# obc-v2_MCU-POWER.net
KiCad netlist of a schematic drawn in Altium Designer
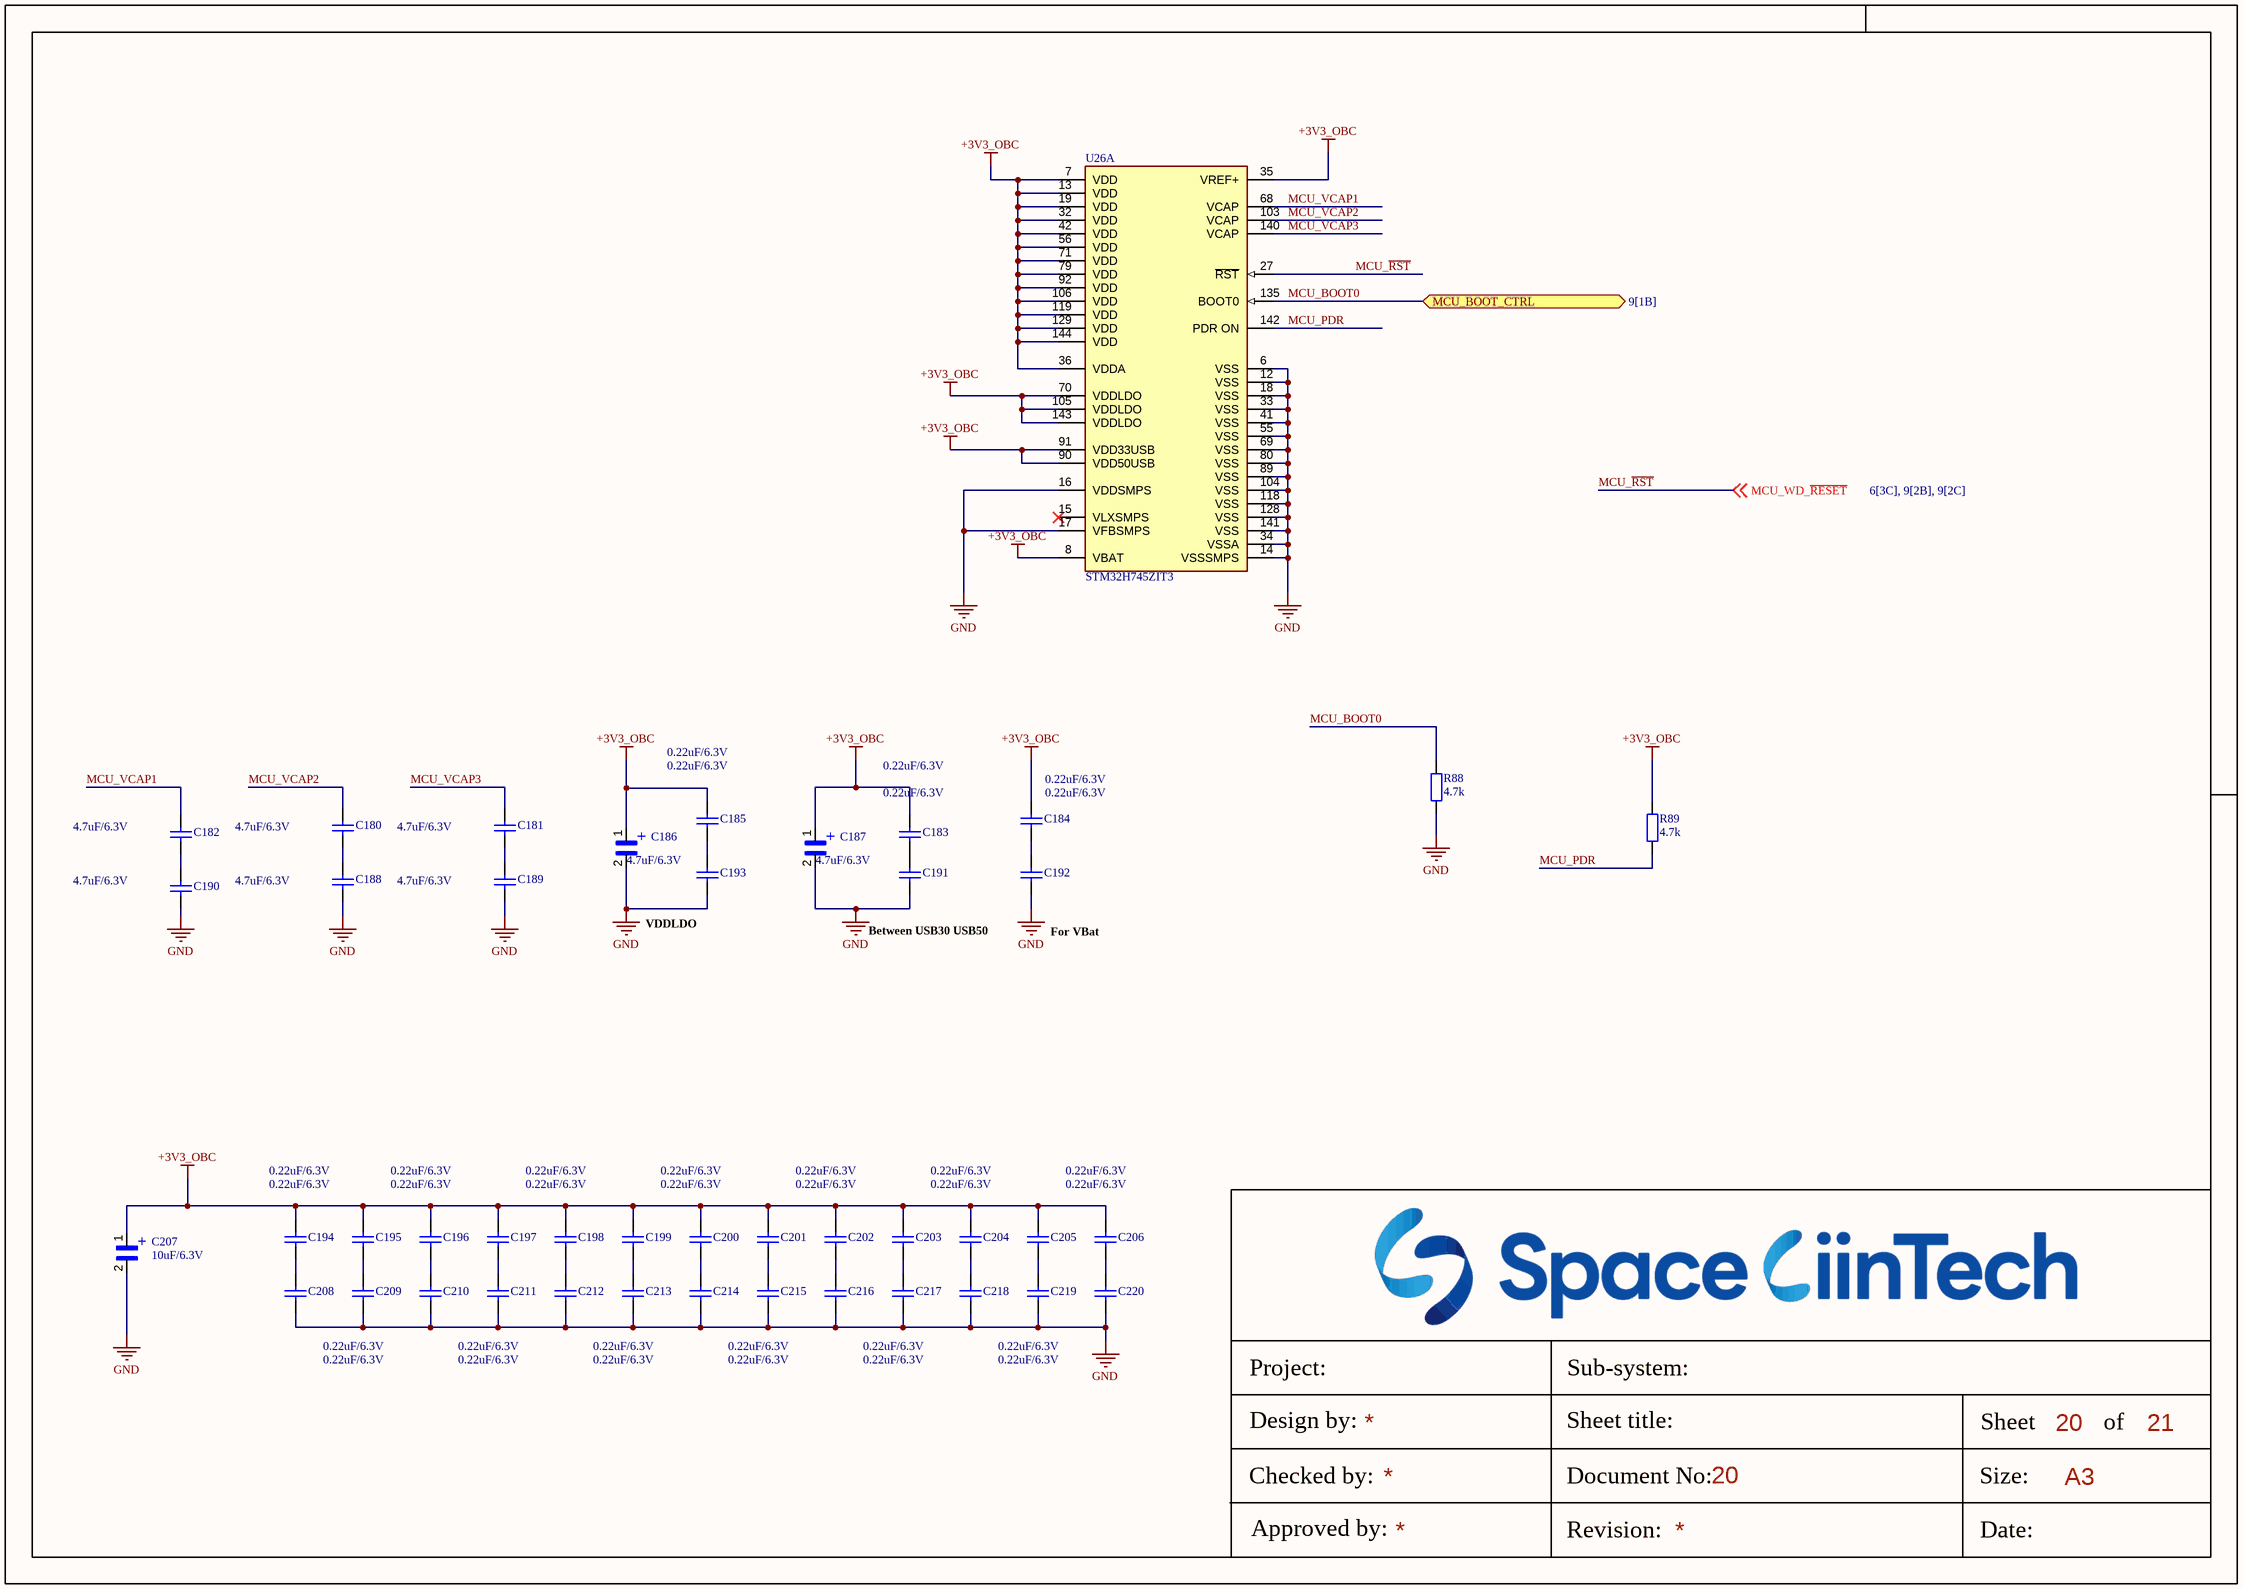
[diagram p0: obc-v2_MCU-POWER.SchDoc]

(export (version "E")
  (design (tool "Eeschema 10.0.6"))
  (components
    (comp (ref "C180")
      (value "4.7uF/6.3V")
      (footprint "CAP_C_1005X60")
      (description "4.7 µF ±20% 6.3V Ceramic Capacitor X7T 0402 (1005 Metric): GRT155D70J475ME13J")
      (libsource (lib "Altium_Lib_by_KhueNguyenCreator") (part "Tu 0402 33nF 10V"))
    )
    (comp (ref "C181")
      (value "4.7uF/6.3V")
      (footprint "CAP_C_1005X60")
      (description "4.7 µF ±20% 6.3V Ceramic Capacitor X7T 0402 (1005 Metric): GRT155D70J475ME13J")
      (libsource (lib "Altium_Lib_by_KhueNguyenCreator") (part "Tu 0402 33nF 10V"))
    )
    (comp (ref "C182")
      (value "4.7uF/6.3V")
      (footprint "CAP_C_1005X60")
      (description "4.7 µF ±20% 6.3V Ceramic Capacitor X7T 0402 (1005 Metric): GRT155D70J475ME13J")
      (libsource (lib "Altium_Lib_by_KhueNguyenCreator") (part "Tu 0402 33nF 10V"))
    )
    (comp (ref "C183")
      (value "0.22uF/6.3V")
      (footprint "CAP_C_1005X60")
      (description "CAPC")
      (libsource (lib "Altium_Lib_by_KhueNguyenCreator") (part "Tu 0402 33nF 10V"))
    )
    (comp (ref "C184")
      (value "0.22uF/6.3V")
      (footprint "CAP_C_1005X60")
      (description "CAPC")
      (libsource (lib "Altium_Lib_by_KhueNguyenCreator") (part "Tu 0402 33nF 10V"))
    )
    (comp (ref "C185")
      (value "0.22uF/6.3V")
      (footprint "CAP_C_1005X60")
      (description "4.7 µF ±20% 6.3V Ceramic Capacitor X7T 0402 (1005 Metric): GRT155D70J475ME13J")
      (libsource (lib "Altium_Lib_by_KhueNguyenCreator") (part "Tu 0402 33nF 10V"))
    )
    (comp (ref "C186")
      (value "4.7uF/6.3V")
      (footprint "CAP_MP_1608X90")
      (description "CAPP")
      (fields (field (name "MP") "TACL335M003RTA"))
      (libsource (lib "TACL335M003RTA") (part "TACL335M003RTA"))
    )
    (comp (ref "C187")
      (value "4.7uF/6.3V")
      (footprint "CAP_MP_1608X90")
      (description "CAPP")
      (fields (field (name "MP") "TACL335M003RTA"))
      (libsource (lib "TACL335M003RTA") (part "TACL335M003RTA"))
    )
    (comp (ref "C188")
      (value "4.7uF/6.3V")
      (footprint "CAP_C_1005X60")
      (description "4.7 µF ±20% 6.3V Ceramic Capacitor X7T 0402 (1005 Metric): GRT155D70J475ME13J")
      (libsource (lib "Altium_Lib_by_KhueNguyenCreator") (part "Tu 0402 33nF 10V"))
    )
    (comp (ref "C189")
      (value "4.7uF/6.3V")
      (footprint "CAP_C_1005X60")
      (description "4.7 µF ±20% 6.3V Ceramic Capacitor X7T 0402 (1005 Metric): GRT155D70J475ME13J")
      (libsource (lib "Altium_Lib_by_KhueNguyenCreator") (part "Tu 0402 33nF 10V"))
    )
    (comp (ref "C190")
      (value "4.7uF/6.3V")
      (footprint "CAP_C_1005X60")
      (description "4.7 µF ±20% 6.3V Ceramic Capacitor X7T 0402 (1005 Metric): GRT155D70J475ME13J")
      (libsource (lib "Altium_Lib_by_KhueNguyenCreator") (part "Tu 0402 33nF 10V"))
    )
    (comp (ref "C191")
      (value "0.22uF/6.3V")
      (footprint "CAP_C_1005X60")
      (description "CAPC")
      (libsource (lib "Altium_Lib_by_KhueNguyenCreator") (part "Tu 0402 33nF 10V"))
    )
    (comp (ref "C192")
      (value "0.22uF/6.3V")
      (footprint "CAP_C_1005X60")
      (description "CAPC")
      (libsource (lib "Altium_Lib_by_KhueNguyenCreator") (part "Tu 0402 33nF 10V"))
    )
    (comp (ref "C193")
      (value "0.22uF/6.3V")
      (footprint "CAP_C_1005X60")
      (description "4.7 µF ±20% 6.3V Ceramic Capacitor X7T 0402 (1005 Metric): GRT155D70J475ME13J")
      (libsource (lib "Altium_Lib_by_KhueNguyenCreator") (part "Tu 0402 33nF 10V"))
    )
    (comp (ref "C194")
      (value "0.22uF/6.3V")
      (footprint "CAP_C_1005X60")
      (description "CAPC")
      (libsource (lib "Altium_Lib_by_KhueNguyenCreator") (part "Tu 0402 33nF 10V"))
    )
    (comp (ref "C195")
      (value "0.22uF/6.3V")
      (footprint "CAP_C_1005X60")
      (description "CAPC")
      (libsource (lib "Altium_Lib_by_KhueNguyenCreator") (part "Tu 0402 33nF 10V"))
    )
    (comp (ref "C196")
      (value "0.22uF/6.3V")
      (footprint "CAP_C_1005X60")
      (description "CAPC")
      (libsource (lib "Altium_Lib_by_KhueNguyenCreator") (part "Tu 0402 33nF 10V"))
    )
    (comp (ref "C197")
      (value "0.22uF/6.3V")
      (footprint "CAP_C_1005X60")
      (description "CAPC")
      (libsource (lib "Altium_Lib_by_KhueNguyenCreator") (part "Tu 0402 33nF 10V"))
    )
    (comp (ref "C198")
      (value "0.22uF/6.3V")
      (footprint "CAP_C_1005X60")
      (description "CAPC")
      (libsource (lib "Altium_Lib_by_KhueNguyenCreator") (part "Tu 0402 33nF 10V"))
    )
    (comp (ref "C199")
      (value "0.22uF/6.3V")
      (footprint "CAP_C_1005X60")
      (description "CAPC")
      (libsource (lib "Altium_Lib_by_KhueNguyenCreator") (part "Tu 0402 33nF 10V"))
    )
    (comp (ref "C200")
      (value "0.22uF/6.3V")
      (footprint "CAP_C_1005X60")
      (description "CAPC")
      (libsource (lib "Altium_Lib_by_KhueNguyenCreator") (part "Tu 0402 33nF 10V"))
    )
    (comp (ref "C201")
      (value "0.22uF/6.3V")
      (footprint "CAP_C_1005X60")
      (description "CAPC")
      (libsource (lib "Altium_Lib_by_KhueNguyenCreator") (part "Tu 0402 33nF 10V"))
    )
    (comp (ref "C202")
      (value "0.22uF/6.3V")
      (footprint "CAP_C_1005X60")
      (description "CAPC")
      (libsource (lib "Altium_Lib_by_KhueNguyenCreator") (part "Tu 0402 33nF 10V"))
    )
    (comp (ref "C203")
      (value "0.22uF/6.3V")
      (footprint "CAP_C_1005X60")
      (description "CAPC")
      (libsource (lib "Altium_Lib_by_KhueNguyenCreator") (part "Tu 0402 33nF 10V"))
    )
    (comp (ref "C204")
      (value "0.22uF/6.3V")
      (footprint "CAP_C_1005X60")
      (description "CAPC")
      (libsource (lib "Altium_Lib_by_KhueNguyenCreator") (part "Tu 0402 33nF 10V"))
    )
    (comp (ref "C205")
      (value "0.22uF/6.3V")
      (footprint "CAP_C_1005X60")
      (description "CAPC")
      (libsource (lib "Altium_Lib_by_KhueNguyenCreator") (part "Tu 0402 33nF 10V"))
    )
    (comp (ref "C206")
      (value "0.22uF/6.3V")
      (footprint "CAP_C_1005X60")
      (description "CAPC")
      (libsource (lib "Altium_Lib_by_KhueNguyenCreator") (part "Tu 0402 33nF 10V"))
    )
    (comp (ref "C207")
      (value "10uF/6.3V")
      (footprint "CAP_MP_2012X170")
      (description "CAPP")
      (fields (field (name "MP") "TACR686M003RTA") (field (name "MF") "AVX"))
      (libsource (lib "TACR686M003RTA") (part "TACR686M003RTA"))
    )
    (comp (ref "C208")
      (value "0.22uF/6.3V")
      (footprint "CAP_C_1005X60")
      (description "CAPC")
      (libsource (lib "Altium_Lib_by_KhueNguyenCreator") (part "Tu 0402 33nF 10V"))
    )
    (comp (ref "C209")
      (value "0.22uF/6.3V")
      (footprint "CAP_C_1005X60")
      (description "CAPC")
      (libsource (lib "Altium_Lib_by_KhueNguyenCreator") (part "Tu 0402 33nF 10V"))
    )
    (comp (ref "C210")
      (value "0.22uF/6.3V")
      (footprint "CAP_C_1005X60")
      (description "CAPC")
      (libsource (lib "Altium_Lib_by_KhueNguyenCreator") (part "Tu 0402 33nF 10V"))
    )
    (comp (ref "C211")
      (value "0.22uF/6.3V")
      (footprint "CAP_C_1005X60")
      (description "CAPC")
      (libsource (lib "Altium_Lib_by_KhueNguyenCreator") (part "Tu 0402 33nF 10V"))
    )
    (comp (ref "C212")
      (value "0.22uF/6.3V")
      (footprint "CAP_C_1005X60")
      (description "CAPC")
      (libsource (lib "Altium_Lib_by_KhueNguyenCreator") (part "Tu 0402 33nF 10V"))
    )
    (comp (ref "C213")
      (value "0.22uF/6.3V")
      (footprint "CAP_C_1005X60")
      (description "CAPC")
      (libsource (lib "Altium_Lib_by_KhueNguyenCreator") (part "Tu 0402 33nF 10V"))
    )
    (comp (ref "C214")
      (value "0.22uF/6.3V")
      (footprint "CAP_C_1005X60")
      (description "CAPC")
      (libsource (lib "Altium_Lib_by_KhueNguyenCreator") (part "Tu 0402 33nF 10V"))
    )
    (comp (ref "C215")
      (value "0.22uF/6.3V")
      (footprint "CAP_C_1005X60")
      (description "CAPC")
      (libsource (lib "Altium_Lib_by_KhueNguyenCreator") (part "Tu 0402 33nF 10V"))
    )
    (comp (ref "C216")
      (value "0.22uF/6.3V")
      (footprint "CAP_C_1005X60")
      (description "CAPC")
      (libsource (lib "Altium_Lib_by_KhueNguyenCreator") (part "Tu 0402 33nF 10V"))
    )
    (comp (ref "C217")
      (value "0.22uF/6.3V")
      (footprint "CAP_C_1005X60")
      (description "CAPC")
      (libsource (lib "Altium_Lib_by_KhueNguyenCreator") (part "Tu 0402 33nF 10V"))
    )
    (comp (ref "C218")
      (value "0.22uF/6.3V")
      (footprint "CAP_C_1005X60")
      (description "CAPC")
      (libsource (lib "Altium_Lib_by_KhueNguyenCreator") (part "Tu 0402 33nF 10V"))
    )
    (comp (ref "C219")
      (value "0.22uF/6.3V")
      (footprint "CAP_C_1005X60")
      (description "CAPC")
      (libsource (lib "Altium_Lib_by_KhueNguyenCreator") (part "Tu 0402 33nF 10V"))
    )
    (comp (ref "C220")
      (value "0.22uF/6.3V")
      (footprint "CAP_C_1005X60")
      (description "CAPC")
      (libsource (lib "Altium_Lib_by_KhueNguyenCreator") (part "Tu 0402 33nF 10V"))
    )
    (comp (ref "R88")
      (value "4.7k")
      (footprint "RES_C_1608X60")
      (description "RES")
      (libsource (lib "Altium_Lib_by_KhueNguyenCreator") (part "Tro 0603 1% 10k"))
    )
    (comp (ref "R89")
      (value "4.7k")
      (footprint "RES_C_1608X60")
      (description "RES")
      (libsource (lib "Altium_Lib_by_KhueNguyenCreator") (part "Tro 0603 1% 10k"))
    )
    (comp (ref "U26")
      (value "STM32H745ZIT3")
      (footprint "FP-LQFP144-1A-MFG")
      (description "HIGH-PERFORMANCE AND DSP WITH DP")
      (fields
        (field (name "MANUFACTURER PART NUMBER") "STM32H745ZIT6")
        (field (name "OCTOPART") "https://octopart.com/stm32h745zit6-stmicroelectronics-100293939")
      )
      (libsource (lib "Altium Content Vault") (part "f5432ce9894f79c0085309acf87c031"))
    )
  )
  (nets
    (net (code "1") (name "+3V3_OBC") (class "Default")
      (node (ref "C183") (pin "1") (pinfunction "1_1") (pintype "passive"))
      (node (ref "C184") (pin "1") (pinfunction "1_1") (pintype "passive"))
      (node (ref "C185") (pin "1") (pinfunction "1_1") (pintype "passive"))
      (node (ref "C186") (pin "1") (pinfunction "1_1") (pintype "passive"))
      (node (ref "C187") (pin "1") (pinfunction "1_1") (pintype "passive"))
      (node (ref "C194") (pin "1") (pinfunction "1_1") (pintype "passive"))
      (node (ref "C195") (pin "1") (pinfunction "1_1") (pintype "passive"))
      (node (ref "C196") (pin "1") (pinfunction "1_1") (pintype "passive"))
      (node (ref "C197") (pin "1") (pinfunction "1_1") (pintype "passive"))
      (node (ref "C198") (pin "1") (pinfunction "1_1") (pintype "passive"))
      (node (ref "C199") (pin "1") (pinfunction "1_1") (pintype "passive"))
      (node (ref "C200") (pin "1") (pinfunction "1_1") (pintype "passive"))
      (node (ref "C201") (pin "1") (pinfunction "1_1") (pintype "passive"))
      (node (ref "C202") (pin "1") (pinfunction "1_1") (pintype "passive"))
      (node (ref "C203") (pin "1") (pinfunction "1_1") (pintype "passive"))
      (node (ref "C204") (pin "1") (pinfunction "1_1") (pintype "passive"))
      (node (ref "C205") (pin "1") (pinfunction "1_1") (pintype "passive"))
      (node (ref "C206") (pin "1") (pinfunction "1_1") (pintype "passive"))
      (node (ref "C207") (pin "1") (pinfunction "1_1") (pintype "passive"))
      (node (ref "R89") (pin "1") (pinfunction "1_1") (pintype "passive"))
      (node (ref "U26") (pin "105") (pinfunction "VDDLDO_105") (pintype "power_in"))
      (node (ref "U26") (pin "106") (pinfunction "VDD_106") (pintype "power_in"))
      (node (ref "U26") (pin "119") (pinfunction "VDD_119") (pintype "power_in"))
      (node (ref "U26") (pin "129") (pinfunction "VDD_129") (pintype "power_in"))
      (node (ref "U26") (pin "13") (pinfunction "VDD_13") (pintype "power_in"))
      (node (ref "U26") (pin "143") (pinfunction "VDDLDO_143") (pintype "power_in"))
      (node (ref "U26") (pin "144") (pinfunction "VDD_144") (pintype "power_in"))
      (node (ref "U26") (pin "19") (pinfunction "VDD_19") (pintype "power_in"))
      (node (ref "U26") (pin "32") (pinfunction "VDD_32") (pintype "power_in"))
      (node (ref "U26") (pin "35") (pinfunction "VREF+_35") (pintype "power_in"))
      (node (ref "U26") (pin "36") (pinfunction "VDDA_36") (pintype "power_in"))
      (node (ref "U26") (pin "42") (pinfunction "VDD_42") (pintype "power_in"))
      (node (ref "U26") (pin "56") (pinfunction "VDD_56") (pintype "power_in"))
      (node (ref "U26") (pin "7") (pinfunction "VDD_7") (pintype "power_in"))
      (node (ref "U26") (pin "70") (pinfunction "VDDLDO_70") (pintype "power_in"))
      (node (ref "U26") (pin "71") (pinfunction "VDD_71") (pintype "power_in"))
      (node (ref "U26") (pin "79") (pinfunction "VDD_79") (pintype "power_in"))
      (node (ref "U26") (pin "8") (pinfunction "VBAT_8") (pintype "power_in"))
      (node (ref "U26") (pin "90") (pinfunction "VDD50USB_90") (pintype "power_in"))
      (node (ref "U26") (pin "91") (pinfunction "VDD33USB_91") (pintype "power_in"))
      (node (ref "U26") (pin "92") (pinfunction "VDD_92") (pintype "power_in"))
    )
    (net (code "2") (name "/MCU_BOOT0") (class "Default")
      (node (ref "R88") (pin "2") (pinfunction "2_2") (pintype "passive"))
      (node (ref "U26") (pin "135") (pinfunction "BOOT0_135") (pintype "input"))
    )
    (net (code "3") (name "/MCU_PDR") (class "Default")
      (node (ref "R89") (pin "2") (pinfunction "2_2") (pintype "passive"))
      (node (ref "U26") (pin "142") (pinfunction "PDR_ON_142") (pintype "passive"))
    )
    (net (code "4") (name "/MCU_VCAP1") (class "Default")
      (node (ref "C182") (pin "1") (pinfunction "1_1") (pintype "passive"))
      (node (ref "U26") (pin "68") (pinfunction "VCAP_68") (pintype "passive"))
    )
    (net (code "5") (name "/MCU_VCAP2") (class "Default")
      (node (ref "C180") (pin "1") (pinfunction "1_1") (pintype "passive"))
      (node (ref "U26") (pin "103") (pinfunction "VCAP_103") (pintype "passive"))
    )
    (net (code "6") (name "/MCU_VCAP3") (class "Default")
      (node (ref "C181") (pin "1") (pinfunction "1_1") (pintype "passive"))
      (node (ref "U26") (pin "140") (pinfunction "VCAP_140") (pintype "passive"))
    )
    (net (code "7") (name "GND") (class "Default")
      (node (ref "C186") (pin "2") (pinfunction "2_2") (pintype "passive"))
      (node (ref "C187") (pin "2") (pinfunction "2_2") (pintype "passive"))
      (node (ref "C188") (pin "2") (pinfunction "2_2") (pintype "passive"))
      (node (ref "C189") (pin "2") (pinfunction "2_2") (pintype "passive"))
      (node (ref "C190") (pin "2") (pinfunction "2_2") (pintype "passive"))
      (node (ref "C191") (pin "2") (pinfunction "2_2") (pintype "passive"))
      (node (ref "C192") (pin "2") (pinfunction "2_2") (pintype "passive"))
      (node (ref "C193") (pin "2") (pinfunction "2_2") (pintype "passive"))
      (node (ref "C207") (pin "2") (pinfunction "2_2") (pintype "passive"))
      (node (ref "C208") (pin "2") (pinfunction "2_2") (pintype "passive"))
      (node (ref "C209") (pin "2") (pinfunction "2_2") (pintype "passive"))
      (node (ref "C210") (pin "2") (pinfunction "2_2") (pintype "passive"))
      (node (ref "C211") (pin "2") (pinfunction "2_2") (pintype "passive"))
      (node (ref "C212") (pin "2") (pinfunction "2_2") (pintype "passive"))
      (node (ref "C213") (pin "2") (pinfunction "2_2") (pintype "passive"))
      (node (ref "C214") (pin "2") (pinfunction "2_2") (pintype "passive"))
      (node (ref "C215") (pin "2") (pinfunction "2_2") (pintype "passive"))
      (node (ref "C216") (pin "2") (pinfunction "2_2") (pintype "passive"))
      (node (ref "C217") (pin "2") (pinfunction "2_2") (pintype "passive"))
      (node (ref "C218") (pin "2") (pinfunction "2_2") (pintype "passive"))
      (node (ref "C219") (pin "2") (pinfunction "2_2") (pintype "passive"))
      (node (ref "C220") (pin "2") (pinfunction "2_2") (pintype "passive"))
      (node (ref "R88") (pin "1") (pinfunction "1_1") (pintype "passive"))
      (node (ref "U26") (pin "104") (pinfunction "VSS_104") (pintype "power_in"))
      (node (ref "U26") (pin "118") (pinfunction "VSS_118") (pintype "power_in"))
      (node (ref "U26") (pin "12") (pinfunction "VSS_12") (pintype "power_in"))
      (node (ref "U26") (pin "128") (pinfunction "VSS_128") (pintype "power_in"))
      (node (ref "U26") (pin "14") (pinfunction "VSSSMPS_14") (pintype "power_in"))
      (node (ref "U26") (pin "141") (pinfunction "VSS_141") (pintype "power_in"))
      (node (ref "U26") (pin "16") (pinfunction "VDDSMPS_16") (pintype "power_in"))
      (node (ref "U26") (pin "17") (pinfunction "VFBSMPS_17") (pintype "power_in"))
      (node (ref "U26") (pin "18") (pinfunction "VSS_18") (pintype "power_in"))
      (node (ref "U26") (pin "33") (pinfunction "VSS_33") (pintype "power_in"))
      (node (ref "U26") (pin "34") (pinfunction "VSSA_34") (pintype "power_in"))
      (node (ref "U26") (pin "41") (pinfunction "VSS_41") (pintype "power_in"))
      (node (ref "U26") (pin "55") (pinfunction "VSS_55") (pintype "power_in"))
      (node (ref "U26") (pin "6") (pinfunction "VSS_6") (pintype "power_in"))
      (node (ref "U26") (pin "69") (pinfunction "VSS_69") (pintype "power_in"))
      (node (ref "U26") (pin "80") (pinfunction "VSS_80") (pintype "power_in"))
      (node (ref "U26") (pin "89") (pinfunction "VSS_89") (pintype "power_in"))
    )
    (net (code "8") (name "MCU_WD_~{RESET}") (class "Default")
      (node (ref "U26") (pin "27") (pinfunction "~{RST}_27") (pintype "input"))
    )
    (net (code "9") (name "Net-(C180-Pad2)") (class "Default")
      (node (ref "C180") (pin "2") (pinfunction "2_2") (pintype "passive"))
      (node (ref "C188") (pin "1") (pinfunction "1_1") (pintype "passive"))
    )
    (net (code "10") (name "Net-(C181-Pad2)") (class "Default")
      (node (ref "C181") (pin "2") (pinfunction "2_2") (pintype "passive"))
      (node (ref "C189") (pin "1") (pinfunction "1_1") (pintype "passive"))
    )
    (net (code "11") (name "Net-(C182-Pad2)") (class "Default")
      (node (ref "C182") (pin "2") (pinfunction "2_2") (pintype "passive"))
      (node (ref "C190") (pin "1") (pinfunction "1_1") (pintype "passive"))
    )
    (net (code "12") (name "Net-(C183-Pad2)") (class "Default")
      (node (ref "C183") (pin "2") (pinfunction "2_2") (pintype "passive"))
      (node (ref "C191") (pin "1") (pinfunction "1_1") (pintype "passive"))
    )
    (net (code "13") (name "Net-(C184-Pad2)") (class "Default")
      (node (ref "C184") (pin "2") (pinfunction "2_2") (pintype "passive"))
      (node (ref "C192") (pin "1") (pinfunction "1_1") (pintype "passive"))
    )
    (net (code "14") (name "Net-(C185-Pad2)") (class "Default")
      (node (ref "C185") (pin "2") (pinfunction "2_2") (pintype "passive"))
      (node (ref "C193") (pin "1") (pinfunction "1_1") (pintype "passive"))
    )
    (net (code "15") (name "Net-(C194-Pad2)") (class "Default")
      (node (ref "C194") (pin "2") (pinfunction "2_2") (pintype "passive"))
      (node (ref "C208") (pin "1") (pinfunction "1_1") (pintype "passive"))
    )
    (net (code "16") (name "Net-(C195-Pad2)") (class "Default")
      (node (ref "C195") (pin "2") (pinfunction "2_2") (pintype "passive"))
      (node (ref "C209") (pin "1") (pinfunction "1_1") (pintype "passive"))
    )
    (net (code "17") (name "Net-(C196-Pad2)") (class "Default")
      (node (ref "C196") (pin "2") (pinfunction "2_2") (pintype "passive"))
      (node (ref "C210") (pin "1") (pinfunction "1_1") (pintype "passive"))
    )
    (net (code "18") (name "Net-(C197-Pad2)") (class "Default")
      (node (ref "C197") (pin "2") (pinfunction "2_2") (pintype "passive"))
      (node (ref "C211") (pin "1") (pinfunction "1_1") (pintype "passive"))
    )
    (net (code "19") (name "Net-(C198-Pad2)") (class "Default")
      (node (ref "C198") (pin "2") (pinfunction "2_2") (pintype "passive"))
      (node (ref "C212") (pin "1") (pinfunction "1_1") (pintype "passive"))
    )
    (net (code "20") (name "Net-(C199-Pad2)") (class "Default")
      (node (ref "C199") (pin "2") (pinfunction "2_2") (pintype "passive"))
      (node (ref "C213") (pin "1") (pinfunction "1_1") (pintype "passive"))
    )
    (net (code "21") (name "Net-(C200-Pad2)") (class "Default")
      (node (ref "C200") (pin "2") (pinfunction "2_2") (pintype "passive"))
      (node (ref "C214") (pin "1") (pinfunction "1_1") (pintype "passive"))
    )
    (net (code "22") (name "Net-(C201-Pad2)") (class "Default")
      (node (ref "C201") (pin "2") (pinfunction "2_2") (pintype "passive"))
      (node (ref "C215") (pin "1") (pinfunction "1_1") (pintype "passive"))
    )
    (net (code "23") (name "Net-(C202-Pad2)") (class "Default")
      (node (ref "C202") (pin "2") (pinfunction "2_2") (pintype "passive"))
      (node (ref "C216") (pin "1") (pinfunction "1_1") (pintype "passive"))
    )
    (net (code "24") (name "Net-(C203-Pad2)") (class "Default")
      (node (ref "C203") (pin "2") (pinfunction "2_2") (pintype "passive"))
      (node (ref "C217") (pin "1") (pinfunction "1_1") (pintype "passive"))
    )
    (net (code "25") (name "Net-(C204-Pad2)") (class "Default")
      (node (ref "C204") (pin "2") (pinfunction "2_2") (pintype "passive"))
      (node (ref "C218") (pin "1") (pinfunction "1_1") (pintype "passive"))
    )
    (net (code "26") (name "Net-(C205-Pad2)") (class "Default")
      (node (ref "C205") (pin "2") (pinfunction "2_2") (pintype "passive"))
      (node (ref "C219") (pin "1") (pinfunction "1_1") (pintype "passive"))
    )
    (net (code "27") (name "Net-(C206-Pad2)") (class "Default")
      (node (ref "C206") (pin "2") (pinfunction "2_2") (pintype "passive"))
      (node (ref "C220") (pin "1") (pinfunction "1_1") (pintype "passive"))
    )
    (net (code "28") (name "unconnected-(U26A-VLXSMPS-Pad15)") (class "Default")
      (node (ref "U26") (pin "15") (pinfunction "VLXSMPS_15") (pintype "power_in+no_connect"))
    )
  )
)
